# OPA4377_V2_0.net
KiCad netlist of a schematic drawn in Altium Designer
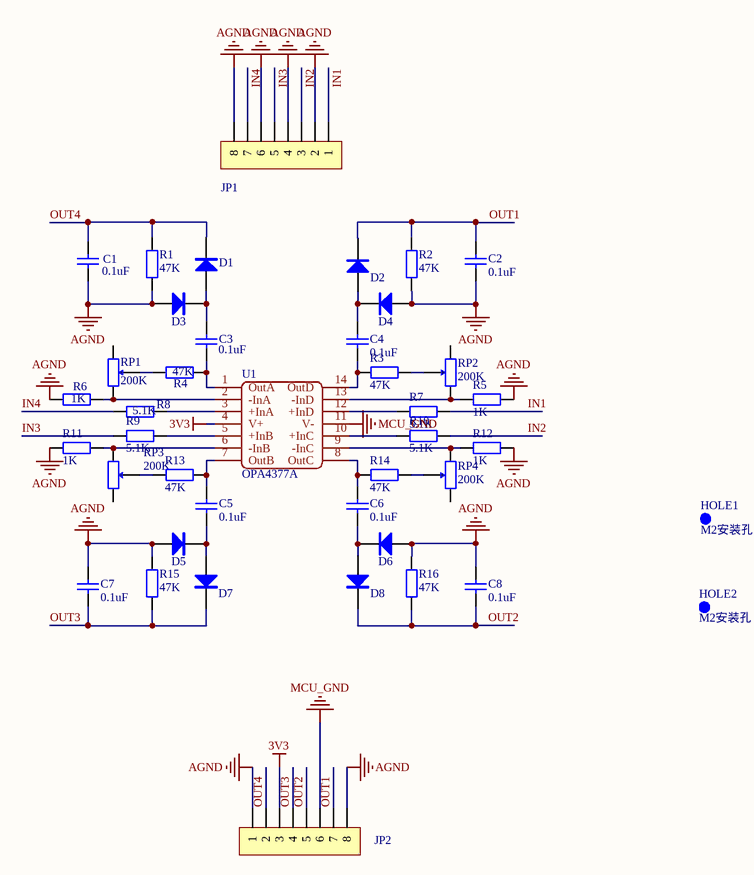
[diagram p0: OPA4377四路 V2.0.SchDoc]

(export (version "E")
  (design (tool "Eeschema 10.0.6"))
  (components
    (comp (ref "C1")
      (value "0.1uF")
      (footprint "C0603_M")
      (description "贴片电容")
      (libsource (lib "0.1 - 电阻-电容-电感-电位器") (part "C"))
    )
    (comp (ref "C2")
      (value "0.1uF")
      (footprint "C0603_M")
      (description "贴片电容")
      (libsource (lib "0.1 - 电阻-电容-电感-电位器") (part "C"))
    )
    (comp (ref "C3")
      (value "0.1uF")
      (footprint "C0603_M")
      (description "贴片电容")
      (libsource (lib "0.1 - 电阻-电容-电感-电位器") (part "C"))
    )
    (comp (ref "C4")
      (value "0.1uF")
      (footprint "C0603_M")
      (description "贴片电容")
      (libsource (lib "0.1 - 电阻-电容-电感-电位器") (part "C"))
    )
    (comp (ref "C5")
      (value "0.1uF")
      (footprint "C0603_M")
      (description "贴片电容")
      (libsource (lib "0.1 - 电阻-电容-电感-电位器") (part "C"))
    )
    (comp (ref "C6")
      (value "0.1uF")
      (footprint "C0603_M")
      (description "贴片电容")
      (libsource (lib "0.1 - 电阻-电容-电感-电位器") (part "C"))
    )
    (comp (ref "C7")
      (value "0.1uF")
      (footprint "C0603_M")
      (description "贴片电容")
      (libsource (lib "0.1 - 电阻-电容-电感-电位器") (part "C"))
    )
    (comp (ref "C8")
      (value "0.1uF")
      (footprint "C0603_M")
      (description "贴片电容")
      (libsource (lib "0.1 - 电阻-电容-电感-电位器") (part "C"))
    )
    (comp (ref "D1")
      (value "1N5819W")
      (footprint "SOD-123")
      (description "肖特基二极管")
      (libsource (lib "0.2 - 二极管-TVS-整流桥") (part "1N5822"))
    )
    (comp (ref "D2")
      (value "1N5819W")
      (footprint "SOD-123")
      (description "肖特基二极管")
      (libsource (lib "0.2 - 二极管-TVS-整流桥") (part "1N5822"))
    )
    (comp (ref "D3")
      (value "1N5819W")
      (footprint "SOD-123")
      (description "肖特基二极管")
      (libsource (lib "0.2 - 二极管-TVS-整流桥") (part "1N5822"))
    )
    (comp (ref "D4")
      (value "1N5819W")
      (footprint "SOD-123")
      (description "肖特基二极管")
      (libsource (lib "0.2 - 二极管-TVS-整流桥") (part "1N5822"))
    )
    (comp (ref "D5")
      (value "1N5819W")
      (footprint "SOD-123")
      (description "肖特基二极管")
      (libsource (lib "0.2 - 二极管-TVS-整流桥") (part "1N5822"))
    )
    (comp (ref "D6")
      (value "1N5819W")
      (footprint "SOD-123")
      (description "肖特基二极管")
      (libsource (lib "0.2 - 二极管-TVS-整流桥") (part "1N5822"))
    )
    (comp (ref "D7")
      (value "1N5819W")
      (footprint "SOD-123")
      (description "肖特基二极管")
      (libsource (lib "0.2 - 二极管-TVS-整流桥") (part "1N5822"))
    )
    (comp (ref "D8")
      (value "1N5819W")
      (footprint "SOD-123")
      (description "肖特基二极管")
      (libsource (lib "0.2 - 二极管-TVS-整流桥") (part "1N5822"))
    )
    (comp (ref "HOLE1") (value "M2安装孔") (footprint "M2安装孔") (libsource (lib "base") (part "M2安装孔")))
    (comp (ref "HOLE2") (value "M2安装孔") (footprint "M2安装孔") (libsource (lib "base") (part "M2安装孔")))
    (comp (ref "JP1")
      (value "FPC1.0-8P")
      (footprint "FPC0.5 2H-WS-8P")
      (description "FPC连接器")
      (fields (field (name "版权归属") "源创客"))
      (libsource (lib "") (part "FPC-8P_1"))
    )
    (comp (ref "JP2")
      (value "FPC1.0-8P")
      (footprint "FPC0.5 2H-WS-8P")
      (description "FPC连接器")
      (fields (field (name "版权归属") "源创客"))
      (libsource (lib "YCK11") (part "FPC-8P"))
    )
    (comp (ref "R1")
      (value "47K")
      (footprint "R0603_M")
      (description "贴片电阻")
      (libsource (lib "0.1 - 电阻-电容-电感-电位器") (part "R"))
    )
    (comp (ref "R2")
      (value "47K")
      (footprint "R0603_M")
      (description "贴片电阻")
      (libsource (lib "0.1 - 电阻-电容-电感-电位器") (part "R"))
    )
    (comp (ref "R3")
      (value "47K")
      (footprint "R0603_M")
      (description "贴片电阻")
      (libsource (lib "0.1 - 电阻-电容-电感-电位器") (part "R"))
    )
    (comp (ref "R4")
      (value "47K")
      (footprint "R0603_M")
      (description "贴片电阻")
      (libsource (lib "0.1 - 电阻-电容-电感-电位器") (part "R"))
    )
    (comp (ref "R5")
      (value "1K")
      (footprint "R0603_M")
      (description "贴片电阻")
      (libsource (lib "0.1 - 电阻-电容-电感-电位器") (part "R"))
    )
    (comp (ref "R6")
      (value "1K")
      (footprint "R0603_M")
      (description "贴片电阻")
      (libsource (lib "0.1 - 电阻-电容-电感-电位器") (part "R"))
    )
    (comp (ref "R7")
      (value "5.1K")
      (footprint "R0603_M")
      (description "贴片电阻")
      (libsource (lib "0.1 - 电阻-电容-电感-电位器") (part "R"))
    )
    (comp (ref "R8")
      (value "5.1K")
      (footprint "R0603_M")
      (description "贴片电阻")
      (libsource (lib "0.1 - 电阻-电容-电感-电位器") (part "R"))
    )
    (comp (ref "R9")
      (value "5.1K")
      (footprint "R0603_M")
      (description "贴片电阻")
      (libsource (lib "0.1 - 电阻-电容-电感-电位器") (part "R"))
    )
    (comp (ref "R10")
      (value "5.1K")
      (footprint "R0603_M")
      (description "贴片电阻")
      (libsource (lib "0.1 - 电阻-电容-电感-电位器") (part "R"))
    )
    (comp (ref "R11")
      (value "1K")
      (footprint "R0603_M")
      (description "贴片电阻")
      (libsource (lib "0.1 - 电阻-电容-电感-电位器") (part "R"))
    )
    (comp (ref "R12")
      (value "1K")
      (footprint "R0603_M")
      (description "贴片电阻")
      (libsource (lib "0.1 - 电阻-电容-电感-电位器") (part "R"))
    )
    (comp (ref "R13")
      (value "47K")
      (footprint "R0603_M")
      (description "贴片电阻")
      (libsource (lib "0.1 - 电阻-电容-电感-电位器") (part "R"))
    )
    (comp (ref "R14")
      (value "47K")
      (footprint "R0603_M")
      (description "贴片电阻")
      (libsource (lib "0.1 - 电阻-电容-电感-电位器") (part "R"))
    )
    (comp (ref "R15")
      (value "47K")
      (footprint "R0603_M")
      (description "贴片电阻")
      (libsource (lib "0.1 - 电阻-电容-电感-电位器") (part "R"))
    )
    (comp (ref "R16")
      (value "47K")
      (footprint "R0603_M")
      (description "贴片电阻")
      (libsource (lib "0.1 - 电阻-电容-电感-电位器") (part "R"))
    )
    (comp (ref "RP1")
      (value "200K")
      (footprint "3362P")
      (description "单联电位器")
      (libsource (lib "0.1 - 电阻-电容-电感-电位器") (part "RP"))
    )
    (comp (ref "RP2")
      (value "200K")
      (footprint "3362P")
      (description "单联电位器")
      (libsource (lib "0.1 - 电阻-电容-电感-电位器") (part "RP"))
    )
    (comp (ref "RP3")
      (value "200K")
      (footprint "3362P")
      (description "单联电位器")
      (libsource (lib "0.1 - 电阻-电容-电感-电位器") (part "RP"))
    )
    (comp (ref "RP4")
      (value "200K")
      (footprint "3362P")
      (description "单联电位器")
      (libsource (lib "0.1 - 电阻-电容-电感-电位器") (part "RP"))
    )
    (comp (ref "U1")
      (value "OPA4377A")
      (footprint "TSSOP14_M")
      (description "OPA4377S四路运放芯片")
      (libsource (lib "电磁及运放") (part "OPA4377A"))
    )
  )
  (nets
    (net (code "1") (name "/IN1") (class "Default")
      (node (ref "JP1") (pin "1") (pinfunction "1_1") (pintype "passive"))
      (node (ref "R7") (pin "1") (pinfunction "1_1") (pintype "passive"))
    )
    (net (code "2") (name "/IN2") (class "Default")
      (node (ref "JP1") (pin "3") (pinfunction "3_3") (pintype "passive"))
      (node (ref "R10") (pin "1") (pinfunction "1_1") (pintype "passive"))
    )
    (net (code "3") (name "/IN3") (class "Default")
      (node (ref "JP1") (pin "5") (pinfunction "5_5") (pintype "passive"))
      (node (ref "R9") (pin "1") (pinfunction "1_1") (pintype "passive"))
    )
    (net (code "4") (name "/IN4") (class "Default")
      (node (ref "JP1") (pin "7") (pinfunction "7_7") (pintype "passive"))
      (node (ref "R8") (pin "1") (pinfunction "1_1") (pintype "passive"))
    )
    (net (code "5") (name "/OUT1") (class "Default")
      (node (ref "C2") (pin "2") (pinfunction "2_2") (pintype "passive"))
      (node (ref "D2") (pin "2") (pinfunction "K_2") (pintype "passive"))
      (node (ref "JP2") (pin "7") (pinfunction "7_7") (pintype "passive"))
      (node (ref "R2") (pin "2") (pinfunction "2_2") (pintype "passive"))
    )
    (net (code "6") (name "/OUT2") (class "Default")
      (node (ref "C8") (pin "2") (pinfunction "2_2") (pintype "passive"))
      (node (ref "D8") (pin "2") (pinfunction "K_2") (pintype "passive"))
      (node (ref "JP2") (pin "5") (pinfunction "5_5") (pintype "passive"))
      (node (ref "R16") (pin "2") (pinfunction "2_2") (pintype "passive"))
    )
    (net (code "7") (name "/OUT3") (class "Default")
      (node (ref "C7") (pin "2") (pinfunction "2_2") (pintype "passive"))
      (node (ref "D7") (pin "2") (pinfunction "K_2") (pintype "passive"))
      (node (ref "JP2") (pin "4") (pinfunction "4_4") (pintype "passive"))
      (node (ref "R15") (pin "2") (pinfunction "2_2") (pintype "passive"))
    )
    (net (code "8") (name "/OUT4") (class "Default")
      (node (ref "C1") (pin "2") (pinfunction "2_2") (pintype "passive"))
      (node (ref "D1") (pin "2") (pinfunction "K_2") (pintype "passive"))
      (node (ref "JP2") (pin "2") (pinfunction "2_2") (pintype "passive"))
      (node (ref "R1") (pin "2") (pinfunction "2_2") (pintype "passive"))
    )
    (net (code "9") (name "3V3") (class "Default")
      (node (ref "JP2") (pin "3") (pinfunction "3_3") (pintype "passive"))
      (node (ref "U1") (pin "4") (pinfunction "V+_4") (pintype "passive"))
    )
    (net (code "10") (name "AGND") (class "Default")
      (node (ref "C1") (pin "1") (pinfunction "1_1") (pintype "passive"))
      (node (ref "C2") (pin "1") (pinfunction "1_1") (pintype "passive"))
      (node (ref "C7") (pin "1") (pinfunction "1_1") (pintype "passive"))
      (node (ref "C8") (pin "1") (pinfunction "1_1") (pintype "passive"))
      (node (ref "D3") (pin "1") (pinfunction "A_1") (pintype "passive"))
      (node (ref "D4") (pin "1") (pinfunction "A_1") (pintype "passive"))
      (node (ref "D5") (pin "1") (pinfunction "A_1") (pintype "passive"))
      (node (ref "D6") (pin "1") (pinfunction "A_1") (pintype "passive"))
      (node (ref "JP1") (pin "2") (pinfunction "2_2") (pintype "passive"))
      (node (ref "JP1") (pin "4") (pinfunction "4_4") (pintype "passive"))
      (node (ref "JP1") (pin "6") (pinfunction "6_6") (pintype "passive"))
      (node (ref "JP1") (pin "8") (pinfunction "8_8") (pintype "passive"))
      (node (ref "JP2") (pin "1") (pinfunction "1_1") (pintype "passive"))
      (node (ref "JP2") (pin "8") (pinfunction "8_8") (pintype "passive"))
      (node (ref "R1") (pin "1") (pinfunction "1_1") (pintype "passive"))
      (node (ref "R11") (pin "1") (pinfunction "1_1") (pintype "passive"))
      (node (ref "R12") (pin "1") (pinfunction "1_1") (pintype "passive"))
      (node (ref "R15") (pin "1") (pinfunction "1_1") (pintype "passive"))
      (node (ref "R16") (pin "1") (pinfunction "1_1") (pintype "passive"))
      (node (ref "R2") (pin "1") (pinfunction "1_1") (pintype "passive"))
      (node (ref "R5") (pin "1") (pinfunction "1_1") (pintype "passive"))
      (node (ref "R6") (pin "1") (pinfunction "1_1") (pintype "passive"))
    )
    (net (code "11") (name "MCU_GND") (class "Default")
      (node (ref "JP2") (pin "6") (pinfunction "6_6") (pintype "passive"))
      (node (ref "U1") (pin "11") (pinfunction "V-_11") (pintype "passive"))
    )
    (net (code "12") (name "Net-(D1-A)") (class "Default")
      (node (ref "C3") (pin "2") (pinfunction "2_2") (pintype "passive"))
      (node (ref "D1") (pin "1") (pinfunction "A_1") (pintype "passive"))
      (node (ref "D3") (pin "2") (pinfunction "K_2") (pintype "passive"))
    )
    (net (code "13") (name "Net-(D2-A)") (class "Default")
      (node (ref "C4") (pin "2") (pinfunction "2_2") (pintype "passive"))
      (node (ref "D2") (pin "1") (pinfunction "A_1") (pintype "passive"))
      (node (ref "D4") (pin "2") (pinfunction "K_2") (pintype "passive"))
    )
    (net (code "14") (name "Net-(D5-K)") (class "Default")
      (node (ref "C5") (pin "2") (pinfunction "2_2") (pintype "passive"))
      (node (ref "D5") (pin "2") (pinfunction "K_2") (pintype "passive"))
      (node (ref "D7") (pin "1") (pinfunction "A_1") (pintype "passive"))
    )
    (net (code "15") (name "Net-(D6-K)") (class "Default")
      (node (ref "C6") (pin "2") (pinfunction "2_2") (pintype "passive"))
      (node (ref "D6") (pin "2") (pinfunction "K_2") (pintype "passive"))
      (node (ref "D8") (pin "1") (pinfunction "A_1") (pintype "passive"))
    )
    (net (code "16") (name "Net-(R3-Pad1)") (class "Default")
      (node (ref "R3") (pin "1") (pinfunction "1_1") (pintype "passive"))
      (node (ref "RP2") (pin "2") (pinfunction "2_2") (pintype "passive"))
    )
    (net (code "17") (name "Net-(R4-Pad1)") (class "Default")
      (node (ref "R4") (pin "1") (pinfunction "1_1") (pintype "passive"))
      (node (ref "RP1") (pin "2") (pinfunction "2_2") (pintype "passive"))
    )
    (net (code "18") (name "Net-(R13-Pad1)") (class "Default")
      (node (ref "R13") (pin "1") (pinfunction "1_1") (pintype "passive"))
      (node (ref "RP3") (pin "2") (pinfunction "2_2") (pintype "passive"))
    )
    (net (code "19") (name "Net-(R14-Pad1)") (class "Default")
      (node (ref "R14") (pin "1") (pinfunction "1_1") (pintype "passive"))
      (node (ref "RP4") (pin "2") (pinfunction "2_2") (pintype "passive"))
    )
    (net (code "20") (name "Net-(U1-+InA)") (class "Default")
      (node (ref "R8") (pin "2") (pinfunction "2_2") (pintype "passive"))
      (node (ref "U1") (pin "3") (pinfunction "+InA_3") (pintype "passive"))
    )
    (net (code "21") (name "Net-(U1-+InB)") (class "Default")
      (node (ref "R9") (pin "2") (pinfunction "2_2") (pintype "passive"))
      (node (ref "U1") (pin "5") (pinfunction "+InB_5") (pintype "passive"))
    )
    (net (code "22") (name "Net-(U1-+InC)") (class "Default")
      (node (ref "R10") (pin "2") (pinfunction "2_2") (pintype "passive"))
      (node (ref "U1") (pin "10") (pinfunction "+InC_10") (pintype "passive"))
    )
    (net (code "23") (name "Net-(U1-+InD)") (class "Default")
      (node (ref "R7") (pin "2") (pinfunction "2_2") (pintype "passive"))
      (node (ref "U1") (pin "12") (pinfunction "+InD_12") (pintype "passive"))
    )
    (net (code "24") (name "Net-(U1--InA)") (class "Default")
      (node (ref "R6") (pin "2") (pinfunction "2_2") (pintype "passive"))
      (node (ref "RP1") (pin "3") (pinfunction "3_3") (pintype "passive"))
      (node (ref "U1") (pin "2") (pinfunction "-InA_2") (pintype "passive"))
    )
    (net (code "25") (name "Net-(U1--InB)") (class "Default")
      (node (ref "R11") (pin "2") (pinfunction "2_2") (pintype "passive"))
      (node (ref "RP3") (pin "3") (pinfunction "3_3") (pintype "passive"))
      (node (ref "U1") (pin "6") (pinfunction "-InB_6") (pintype "passive"))
    )
    (net (code "26") (name "Net-(U1--InC)") (class "Default")
      (node (ref "R12") (pin "2") (pinfunction "2_2") (pintype "passive"))
      (node (ref "RP4") (pin "3") (pinfunction "3_3") (pintype "passive"))
      (node (ref "U1") (pin "9") (pinfunction "-InC_9") (pintype "passive"))
    )
    (net (code "27") (name "Net-(U1--InD)") (class "Default")
      (node (ref "R5") (pin "2") (pinfunction "2_2") (pintype "passive"))
      (node (ref "RP2") (pin "3") (pinfunction "3_3") (pintype "passive"))
      (node (ref "U1") (pin "13") (pinfunction "-InD_13") (pintype "passive"))
    )
    (net (code "28") (name "Net-(U1-OutA)") (class "Default")
      (node (ref "C3") (pin "1") (pinfunction "1_1") (pintype "passive"))
      (node (ref "R4") (pin "2") (pinfunction "2_2") (pintype "passive"))
      (node (ref "U1") (pin "1") (pinfunction "OutA_1") (pintype "passive"))
    )
    (net (code "29") (name "Net-(U1-OutB)") (class "Default")
      (node (ref "C5") (pin "1") (pinfunction "1_1") (pintype "passive"))
      (node (ref "R13") (pin "2") (pinfunction "2_2") (pintype "passive"))
      (node (ref "U1") (pin "7") (pinfunction "OutB_7") (pintype "passive"))
    )
    (net (code "30") (name "Net-(U1-OutC)") (class "Default")
      (node (ref "C6") (pin "1") (pinfunction "1_1") (pintype "passive"))
      (node (ref "R14") (pin "2") (pinfunction "2_2") (pintype "passive"))
      (node (ref "U1") (pin "8") (pinfunction "OutC_8") (pintype "passive"))
    )
    (net (code "31") (name "Net-(U1-OutD)") (class "Default")
      (node (ref "C4") (pin "1") (pinfunction "1_1") (pintype "passive"))
      (node (ref "R3") (pin "2") (pinfunction "2_2") (pintype "passive"))
      (node (ref "U1") (pin "14") (pinfunction "OutD_14") (pintype "passive"))
    )
    (net (code "32") (name "unconnected-(RP1-Pad1)") (class "Default")
      (node (ref "RP1") (pin "1") (pinfunction "1_1") (pintype "passive"))
    )
    (net (code "33") (name "unconnected-(RP2-Pad1)") (class "Default")
      (node (ref "RP2") (pin "1") (pinfunction "1_1") (pintype "passive"))
    )
    (net (code "34") (name "unconnected-(RP3-Pad1)") (class "Default")
      (node (ref "RP3") (pin "1") (pinfunction "1_1") (pintype "passive"))
    )
    (net (code "35") (name "unconnected-(RP4-Pad1)") (class "Default")
      (node (ref "RP4") (pin "1") (pinfunction "1_1") (pintype "passive"))
    )
  )
)
